# usblighteagle.net
KiCad netlist of a schematic drawn in EAGLE
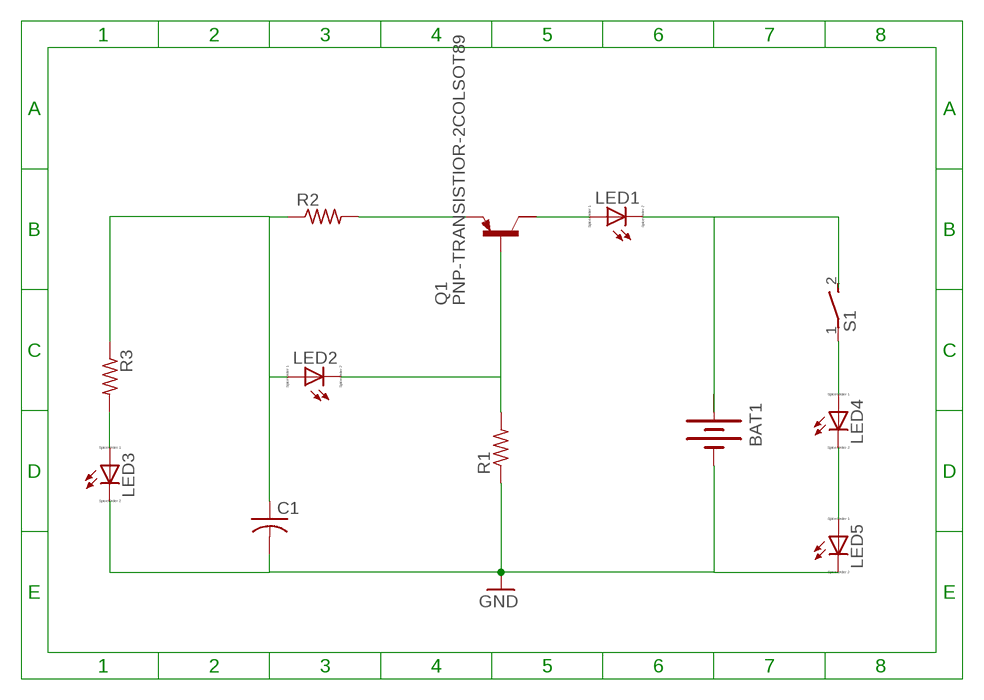
[diagram p0: schematic, sheet 1]

(export (version "E")
  (design (tool "Eeschema 10.0.6"))
  (components
    (comp (ref "BAT1")
      (value "BATTERY")
      (footprint "eagle-import:BATTERY")
      (libsource (lib "eagle-import") (part "BATTERY"))
    )
    (comp (ref "C1")
      (value "C-US025-024X044")
      (footprint "eagle-import:C025-024X044")
      (libsource (lib "eagle-import") (part "C-US025-024X044"))
    )
    (comp (ref "LED1")
      (value "LED_E")
      (footprint "eagle-import:LED_1206")
      (libsource (lib "eagle-import") (part "LED_E"))
    )
    (comp (ref "LED2")
      (value "LED_E")
      (footprint "eagle-import:LED_1206")
      (libsource (lib "eagle-import") (part "LED_E"))
    )
    (comp (ref "LED3")
      (value "LED_E")
      (footprint "eagle-import:LED_1206")
      (libsource (lib "eagle-import") (part "LED_E"))
    )
    (comp (ref "LED4")
      (value "LED_E")
      (footprint "eagle-import:LED_1206")
      (libsource (lib "eagle-import") (part "LED_E"))
    )
    (comp (ref "LED5")
      (value "LED_E")
      (footprint "eagle-import:LED_1206")
      (libsource (lib "eagle-import") (part "LED_E"))
    )
    (comp (ref "Q1")
      (value "PNP-TRANSISTIOR-2COLSOT89")
      (footprint "eagle-import:SOT89")
      (libsource (lib "eagle-import") (part "PNP-TRANSISTIOR-2COLSOT89"))
    )
    (comp (ref "R1")
      (value "R-US_0204/2V")
      (footprint "eagle-import:0204V")
      (libsource (lib "eagle-import") (part "R-US_0204/2V"))
    )
    (comp (ref "R2")
      (value "R-US_0204/2V")
      (footprint "eagle-import:0204V")
      (libsource (lib "eagle-import") (part "R-US_0204/2V"))
    )
    (comp (ref "R3")
      (value "R-US_0204/2V")
      (footprint "eagle-import:0204V")
      (libsource (lib "eagle-import") (part "R-US_0204/2V"))
    )
    (comp (ref "S1")
      (value "DS01E")
      (footprint "eagle-import:DS-01")
      (libsource (lib "eagle-import") (part "DS01E"))
    )
  )
  (nets
    (net (code "1") (name "/+") (class "Default")
      (node (ref "BAT1") (pin "+") (pinfunction "+_+") (pintype "power_in"))
    )
    (net (code "2") (name "GND") (class "Default")
      (node (ref "BAT1") (pin "-") (pinfunction "-_-") (pintype "power_in"))
      (node (ref "C1") (pin "2") (pinfunction "2_2") (pintype "passive"))
      (node (ref "LED3") (pin "C") (pinfunction "C_C") (pintype "passive"))
      (node (ref "LED5") (pin "C") (pinfunction "C_C") (pintype "passive"))
      (node (ref "R1") (pin "1") (pinfunction "1_1") (pintype "passive"))
    )
    (net (code "3") (name "Net-(BAT1-+-Pad+@1)") (class "Default")
      (node (ref "BAT1") (pin "+@1") (pinfunction "+_+@1") (pintype "power_in"))
      (node (ref "LED1") (pin "C") (pinfunction "C_C") (pintype "passive"))
    )
    (net (code "4") (name "Net-(C1-Pad1)") (class "Default")
      (node (ref "C1") (pin "1") (pinfunction "1_1") (pintype "passive"))
      (node (ref "LED2") (pin "A") (pinfunction "A_A") (pintype "passive"))
      (node (ref "R2") (pin "1") (pinfunction "1_1") (pintype "passive"))
      (node (ref "R3") (pin "1") (pinfunction "1_1") (pintype "passive"))
    )
    (net (code "5") (name "Net-(LED3-PadA)") (class "Default")
      (node (ref "LED3") (pin "A") (pinfunction "A_A") (pintype "passive"))
      (node (ref "R3") (pin "2") (pinfunction "2_2") (pintype "passive"))
    )
    (net (code "6") (name "Net-(LED4-PadA)") (class "Default")
      (node (ref "LED4") (pin "A") (pinfunction "A_A") (pintype "passive"))
      (node (ref "S1") (pin "1") (pinfunction "1_1") (pintype "passive"))
    )
    (net (code "7") (name "Net-(LED4-PadC)") (class "Default")
      (node (ref "LED4") (pin "C") (pinfunction "C_C") (pintype "passive"))
      (node (ref "LED5") (pin "A") (pinfunction "A_A") (pintype "passive"))
    )
    (net (code "8") (name "Net-(Q1-B)") (class "Default")
      (node (ref "LED2") (pin "C") (pinfunction "C_C") (pintype "passive"))
      (node (ref "Q1") (pin "1") (pinfunction "B_1") (pintype "passive"))
      (node (ref "R1") (pin "2") (pinfunction "2_2") (pintype "passive"))
    )
    (net (code "9") (name "Net-(Q1-C)") (class "Default")
      (node (ref "LED1") (pin "A") (pinfunction "A_A") (pintype "passive"))
      (node (ref "Q1") (pin "2") (pinfunction "C_2") (pintype "passive"))
    )
    (net (code "10") (name "Net-(Q1-E)") (class "Default")
      (node (ref "Q1") (pin "3") (pinfunction "E_3") (pintype "passive"))
      (node (ref "R2") (pin "2") (pinfunction "2_2") (pintype "passive"))
    )
    (net (code "11") (name "unconnected-(Q1-C{slash}-Pad2@1)") (class "Default")
      (node (ref "Q1") (pin "2@1") (pinfunction "C/_2@1") (pintype "passive"))
    )
    (net (code "12") (name "unconnected-(S1-Pad2)") (class "Default")
      (node (ref "S1") (pin "2") (pinfunction "2_2") (pintype "passive"))
    )
  )
)
